# Adafruit_MCP4725.net
KiCad netlist of a schematic drawn in EAGLE
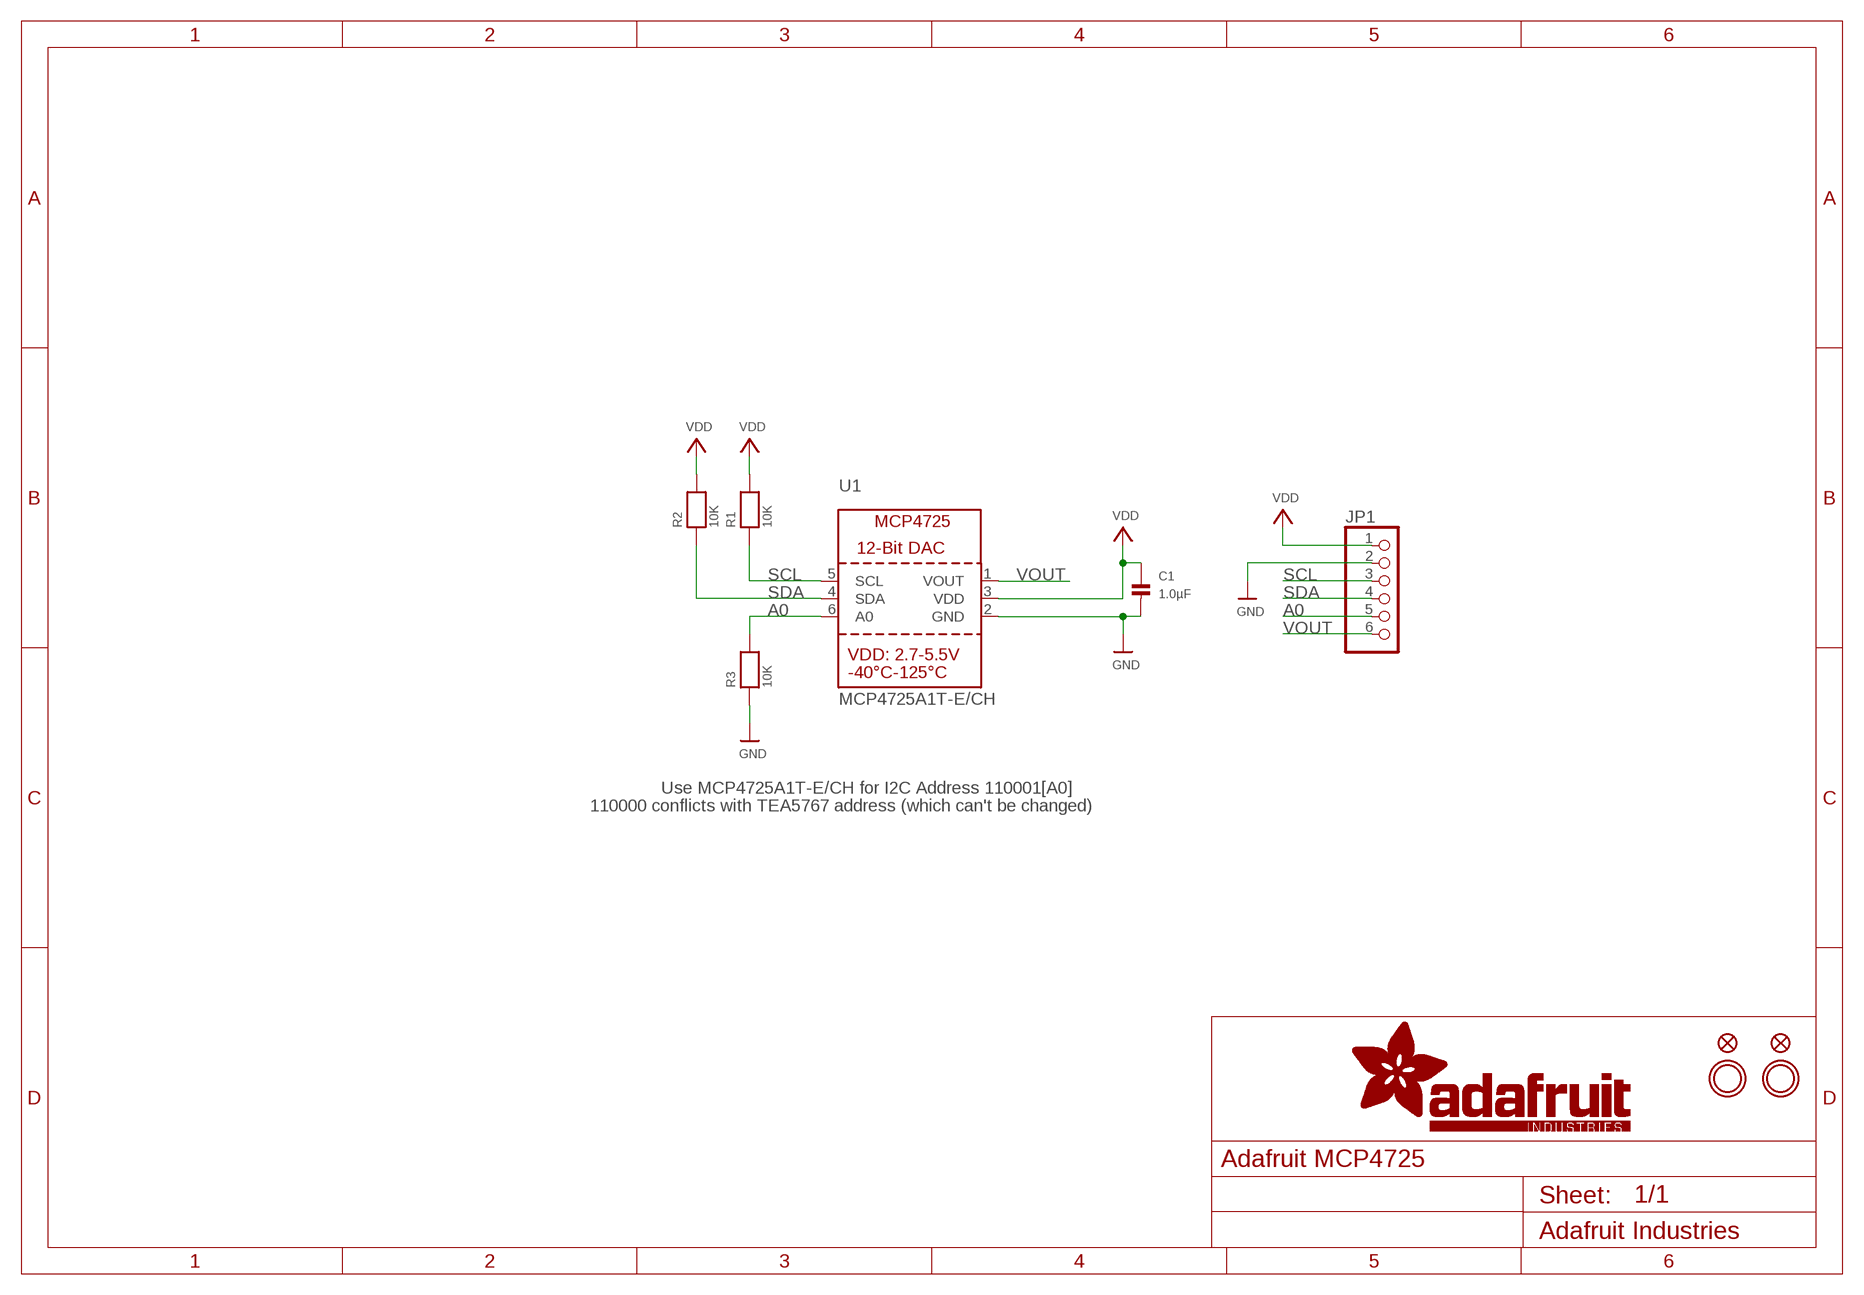
[diagram p0: schematic, sheet 1]

(export (version "E")
  (design (tool "Eeschema 10.0.6"))
  (components
    (comp (ref "C1")
      (value "1.0µF")
      (footprint "eagle-import:0805")
      (libsource (lib "eagle-import") (part "CAP_CERAMIC0805"))
    )
    (comp (ref "FID1")
      (value "FIDUCIAL\"\"")
      (footprint "eagle-import:FIDUCIAL_1MM")
      (libsource (lib "eagle-import") (part "FIDUCIAL{dblquote}{dblquote}"))
    )
    (comp (ref "FID2")
      (value "FIDUCIAL\"\"")
      (footprint "eagle-import:FIDUCIAL_1MM")
      (libsource (lib "eagle-import") (part "FIDUCIAL{dblquote}{dblquote}"))
    )
    (comp (ref "JP1")
      (value "HEADER-1X670MIL")
      (footprint "eagle-import:1X06_ROUND_70")
      (libsource (lib "eagle-import") (part "HEADER-1X670MIL"))
    )
    (comp (ref "R1")
      (value "10K")
      (footprint "eagle-import:0805")
      (libsource (lib "eagle-import") (part "RESISTOR0805"))
    )
    (comp (ref "R2")
      (value "10K")
      (footprint "eagle-import:0805")
      (libsource (lib "eagle-import") (part "RESISTOR0805"))
    )
    (comp (ref "R3")
      (value "10K")
      (footprint "eagle-import:0805")
      (libsource (lib "eagle-import") (part "RESISTOR0805"))
    )
    (comp (ref "U$7")
      (value "MOUNTINGHOLE2.5")
      (footprint "eagle-import:MOUNTINGHOLE_2.5_PLATED")
      (libsource (lib "eagle-import") (part "MOUNTINGHOLE2.5"))
    )
    (comp (ref "U$8")
      (value "MOUNTINGHOLE2.5")
      (footprint "eagle-import:MOUNTINGHOLE_2.5_PLATED")
      (libsource (lib "eagle-import") (part "MOUNTINGHOLE2.5"))
    )
    (comp (ref "U1")
      (value "MCP4725A1T-E/CH")
      (footprint "eagle-import:SOT23-6")
      (libsource (lib "eagle-import") (part "DAC_MCP4725"))
    )
  )
  (nets
    (net (code "1") (name "/A0") (class "Default")
      (node (ref "JP1") (pin "5") (pinfunction "5_5") (pintype "passive"))
      (node (ref "R3") (pin "2") (pinfunction "2_2") (pintype "passive"))
      (node (ref "U1") (pin "6") (pinfunction "A0_6") (pintype "input"))
    )
    (net (code "2") (name "/SCL") (class "Default")
      (node (ref "JP1") (pin "3") (pinfunction "3_3") (pintype "passive"))
      (node (ref "R1") (pin "1") (pinfunction "1_1") (pintype "passive"))
      (node (ref "U1") (pin "5") (pinfunction "SCL_5") (pintype "bidirectional"))
    )
    (net (code "3") (name "/SDA") (class "Default")
      (node (ref "JP1") (pin "4") (pinfunction "4_4") (pintype "passive"))
      (node (ref "R2") (pin "1") (pinfunction "1_1") (pintype "passive"))
      (node (ref "U1") (pin "4") (pinfunction "SDA_4") (pintype "bidirectional"))
    )
    (net (code "4") (name "/VOUT") (class "Default")
      (node (ref "JP1") (pin "6") (pinfunction "6_6") (pintype "passive"))
      (node (ref "U1") (pin "1") (pinfunction "VOUT_1") (pintype "output"))
    )
    (net (code "5") (name "GND") (class "Default")
      (node (ref "C1") (pin "2") (pinfunction "P$2_2") (pintype "passive"))
      (node (ref "JP1") (pin "2") (pinfunction "2_2") (pintype "passive"))
      (node (ref "R3") (pin "1") (pinfunction "1_1") (pintype "passive"))
      (node (ref "U1") (pin "2") (pinfunction "GND_2") (pintype "power_in"))
    )
    (net (code "6") (name "VDD") (class "Default")
      (node (ref "C1") (pin "1") (pinfunction "P$1_1") (pintype "passive"))
      (node (ref "JP1") (pin "1") (pinfunction "1_1") (pintype "passive"))
      (node (ref "R1") (pin "2") (pinfunction "2_2") (pintype "passive"))
      (node (ref "R2") (pin "2") (pinfunction "2_2") (pintype "passive"))
      (node (ref "U1") (pin "3") (pinfunction "VDD_3") (pintype "power_in"))
    )
  )
)
